# rapidshark-flywheel-controller-mk-1_1.net
KiCad netlist of a schematic drawn in EAGLE
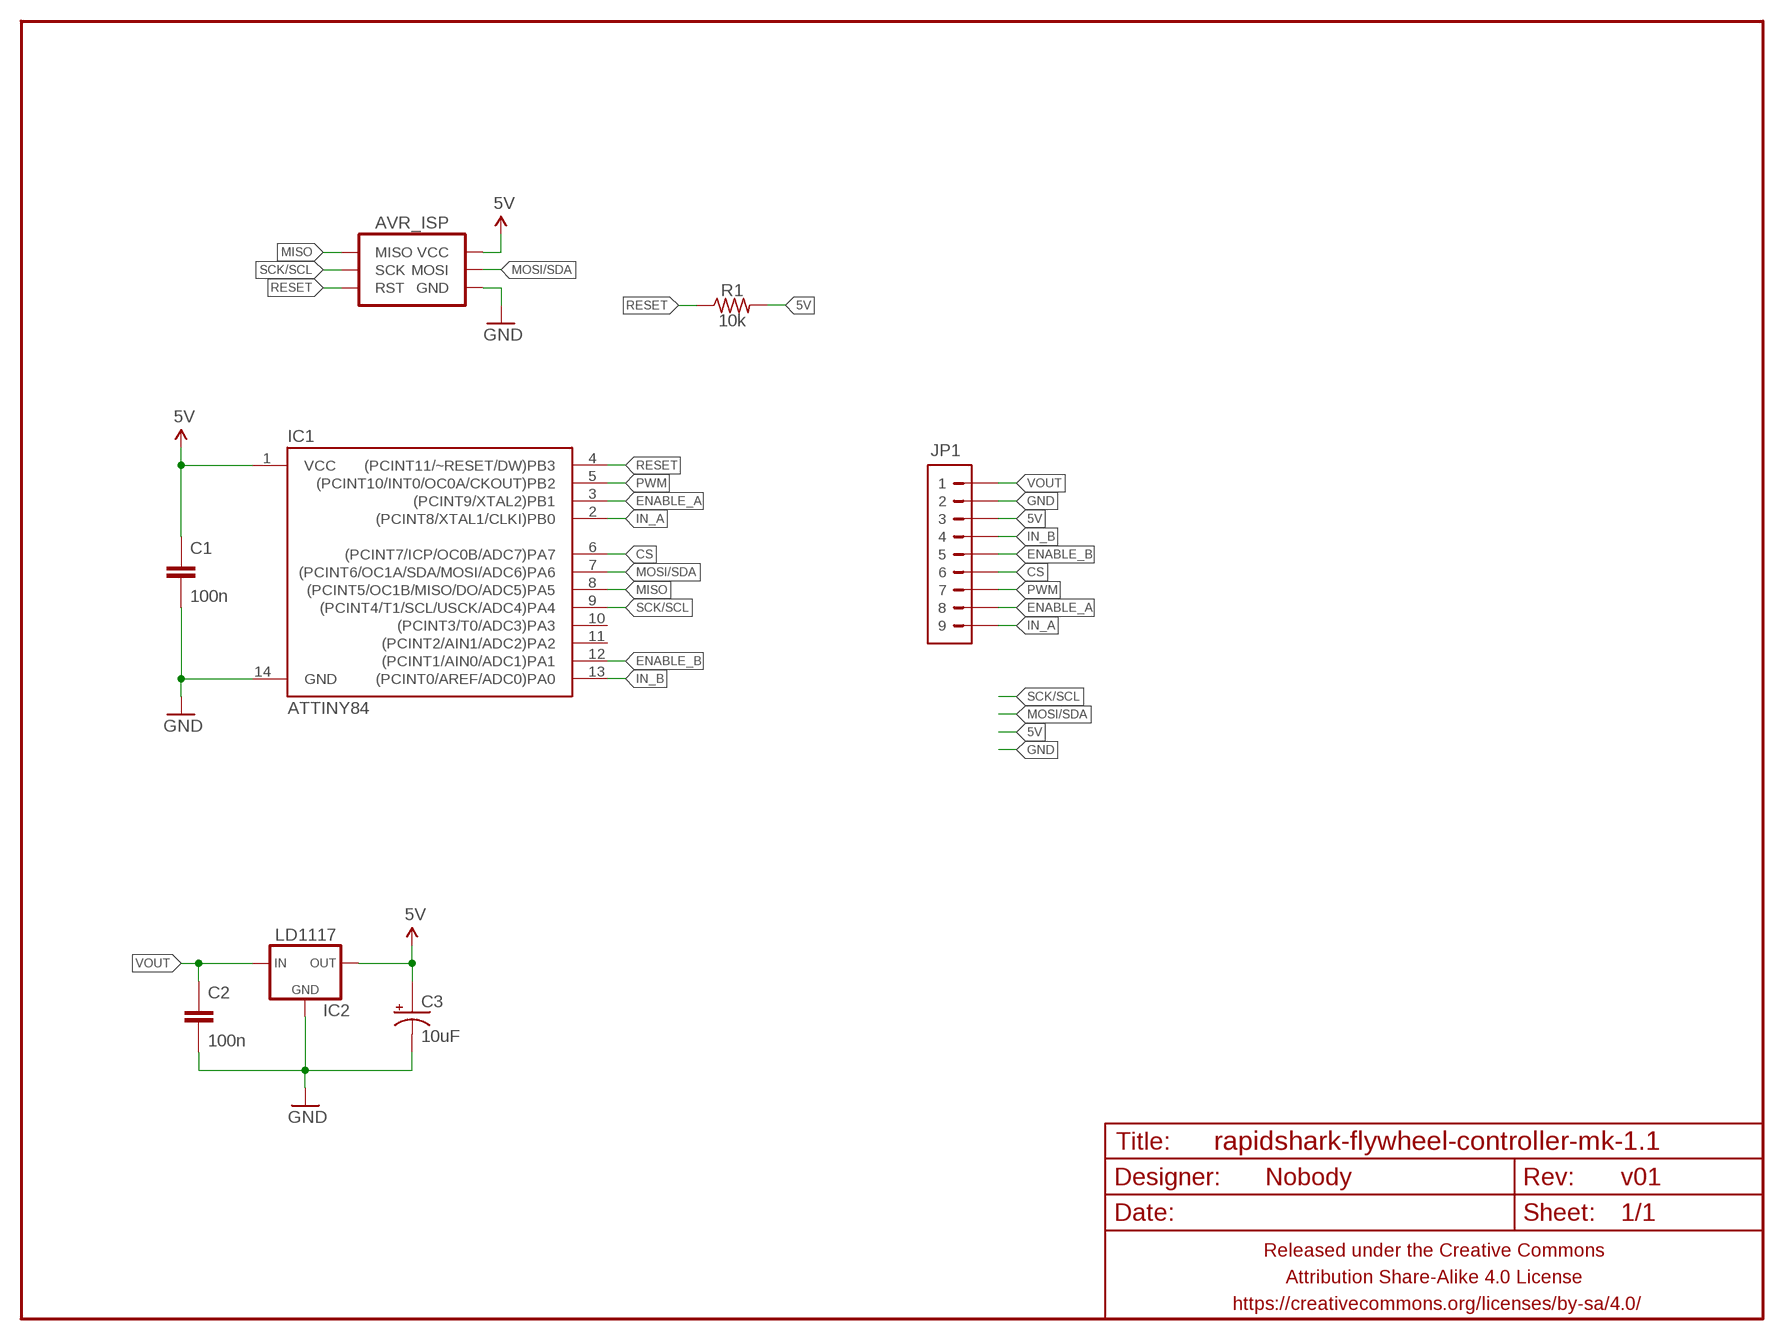
[diagram p0: schematic, sheet 1]

(export (version "E")
  (design (tool "Eeschema 10.0.6"))
  (components
    (comp (ref "AVR_ISP")
      (value "AVR_SPI_PRG_6JST-PH-VERT-PTH")
      (footprint "eagle-import:JST-6-PH-VERT-PTH")
      (libsource (lib "eagle-import") (part "AVR_SPI_PRG_6JST-PH-VERT-PTH"))
    )
    (comp (ref "C1")
      (value "100n")
      (footprint "eagle-import:C0805")
      (libsource (lib "eagle-import") (part "CAPACITOR-CERAMICC0805"))
    )
    (comp (ref "C2")
      (value "100n")
      (footprint "eagle-import:C0805")
      (libsource (lib "eagle-import") (part "CAPACITOR-CERAMICC0805"))
    )
    (comp (ref "C3")
      (value "10uF")
      (footprint "eagle-import:E2-5")
      (libsource (lib "eagle-import") (part "CAPACITOR-POLARIZEDE2-5"))
    )
    (comp (ref "FRAME1")
      (value "FRAME-LETTERNO_PACKAGE")
      (footprint "eagle-import:DUMMY")
      (fields (field (name "DESIGNER") "Nobody"))
      (libsource (lib "eagle-import") (part "FRAME-LETTERNO_PACKAGE"))
    )
    (comp (ref "IC1")
      (value "ATTINY84")
      (footprint "eagle-import:SO14")
      (libsource (lib "eagle-import") (part "ATTINY84"))
    )
    (comp (ref "IC2")
      (value "LD1117")
      (footprint "eagle-import:SOT223")
      (libsource (lib "eagle-import") (part "V_REG_78XXSOT-223"))
    )
    (comp (ref "JP1")
      (value "M09CENTERED")
      (footprint "eagle-import:1X09-CENTERED")
      (libsource (lib "eagle-import") (part "M09CENTERED"))
    )
    (comp (ref "R1")
      (value "10k")
      (footprint "eagle-import:R0805")
      (libsource (lib "eagle-import") (part "RESISTORR0805"))
    )
  )
  (nets
    (net (code "1") (name "5V") (class "Default")
      (node (ref "AVR_ISP") (pin "2") (pinfunction "VCC_2") (pintype "passive"))
      (node (ref "C1") (pin "1") (pinfunction "1_1") (pintype "passive"))
      (node (ref "C3") (pin "+") (pinfunction "+_+") (pintype "passive"))
      (node (ref "IC1") (pin "1") (pinfunction "VCC_1") (pintype "bidirectional"))
      (node (ref "IC2") (pin "2") (pinfunction "OUT_2") (pintype "bidirectional"))
      (node (ref "IC2") (pin "4") (pinfunction "OUT_4") (pintype "bidirectional"))
      (node (ref "JP1") (pin "3") (pinfunction "3_3") (pintype "bidirectional"))
      (node (ref "R1") (pin "2") (pinfunction "2_2") (pintype "passive"))
    )
    (net (code "2") (name "CS") (class "Default")
      (node (ref "IC1") (pin "6") (pinfunction "(PCINT7/ICP/OC0B/ADC7)PA7_6") (pintype "bidirectional"))
      (node (ref "JP1") (pin "6") (pinfunction "6_6") (pintype "bidirectional"))
    )
    (net (code "3") (name "ENABLE_A") (class "Default")
      (node (ref "IC1") (pin "3") (pinfunction "(PCINT9/XTAL2)PB1_3") (pintype "bidirectional"))
      (node (ref "JP1") (pin "8") (pinfunction "8_8") (pintype "bidirectional"))
    )
    (net (code "4") (name "ENABLE_B") (class "Default")
      (node (ref "IC1") (pin "12") (pinfunction "(PCINT1/AIN0/ADC1)PA1_12") (pintype "bidirectional"))
      (node (ref "JP1") (pin "5") (pinfunction "5_5") (pintype "bidirectional"))
    )
    (net (code "5") (name "GND") (class "Default")
      (node (ref "AVR_ISP") (pin "6") (pinfunction "GND_6") (pintype "passive"))
      (node (ref "C1") (pin "2") (pinfunction "2_2") (pintype "passive"))
      (node (ref "C2") (pin "2") (pinfunction "2_2") (pintype "passive"))
      (node (ref "C3") (pin "-") (pinfunction "-_-") (pintype "passive"))
      (node (ref "IC1") (pin "14") (pinfunction "GND_14") (pintype "bidirectional"))
      (node (ref "IC2") (pin "1") (pinfunction "GND_1") (pintype "bidirectional"))
      (node (ref "JP1") (pin "2") (pinfunction "2_2") (pintype "bidirectional"))
    )
    (net (code "6") (name "IN_A") (class "Default")
      (node (ref "IC1") (pin "2") (pinfunction "(PCINT8/XTAL1/CLKI)PB0_2") (pintype "bidirectional"))
      (node (ref "JP1") (pin "9") (pinfunction "9_9") (pintype "bidirectional"))
    )
    (net (code "7") (name "IN_B") (class "Default")
      (node (ref "IC1") (pin "13") (pinfunction "(PCINT0/AREF/ADC0)PA0_13") (pintype "bidirectional"))
      (node (ref "JP1") (pin "4") (pinfunction "4_4") (pintype "bidirectional"))
    )
    (net (code "8") (name "MISO") (class "Default")
      (node (ref "AVR_ISP") (pin "1") (pinfunction "MISO_1") (pintype "passive"))
      (node (ref "IC1") (pin "8") (pinfunction "(PCINT5/OC1B/MISO/DO/ADC5)PA5_8") (pintype "bidirectional"))
    )
    (net (code "9") (name "MOSI{slash}SDA") (class "Default")
      (node (ref "AVR_ISP") (pin "4") (pinfunction "MOSI_4") (pintype "passive"))
      (node (ref "IC1") (pin "7") (pinfunction "(PCINT6/OC1A/SDA/MOSI/ADC6)PA6_7") (pintype "bidirectional"))
    )
    (net (code "10") (name "PWM") (class "Default")
      (node (ref "IC1") (pin "5") (pinfunction "(PCINT10/INT0/OC0A/CKOUT)PB2_5") (pintype "bidirectional"))
      (node (ref "JP1") (pin "7") (pinfunction "7_7") (pintype "bidirectional"))
    )
    (net (code "11") (name "RESET") (class "Default")
      (node (ref "AVR_ISP") (pin "5") (pinfunction "RST_5") (pintype "passive"))
      (node (ref "IC1") (pin "4") (pinfunction "(PCINT11/~{RESET/DW})PB3_4") (pintype "bidirectional"))
      (node (ref "R1") (pin "1") (pinfunction "1_1") (pintype "passive"))
    )
    (net (code "12") (name "SCK{slash}SCL") (class "Default")
      (node (ref "AVR_ISP") (pin "3") (pinfunction "SCK_3") (pintype "passive"))
      (node (ref "IC1") (pin "9") (pinfunction "(PCINT4/T1/SCL/USCK/ADC4)PA4_9") (pintype "bidirectional"))
    )
    (net (code "13") (name "VOUT") (class "Default")
      (node (ref "C2") (pin "1") (pinfunction "1_1") (pintype "passive"))
      (node (ref "IC2") (pin "3") (pinfunction "IN_3") (pintype "bidirectional"))
      (node (ref "JP1") (pin "1") (pinfunction "1_1") (pintype "bidirectional"))
    )
    (net (code "14") (name "unconnected-(IC1-(PCINT2{slash}AIN1{slash}ADC2)PA2-Pad11)") (class "Default")
      (node (ref "IC1") (pin "11") (pinfunction "(PCINT2/AIN1/ADC2)PA2_11") (pintype "bidirectional"))
    )
    (net (code "15") (name "unconnected-(IC1-(PCINT3{slash}T0{slash}ADC3)PA3-Pad10)") (class "Default")
      (node (ref "IC1") (pin "10") (pinfunction "(PCINT3/T0/ADC3)PA3_10") (pintype "bidirectional"))
    )
  )
)
